# MCU098_05_XDS110_Target_Interface.net
KiCad netlist of a schematic drawn in Altium Designer
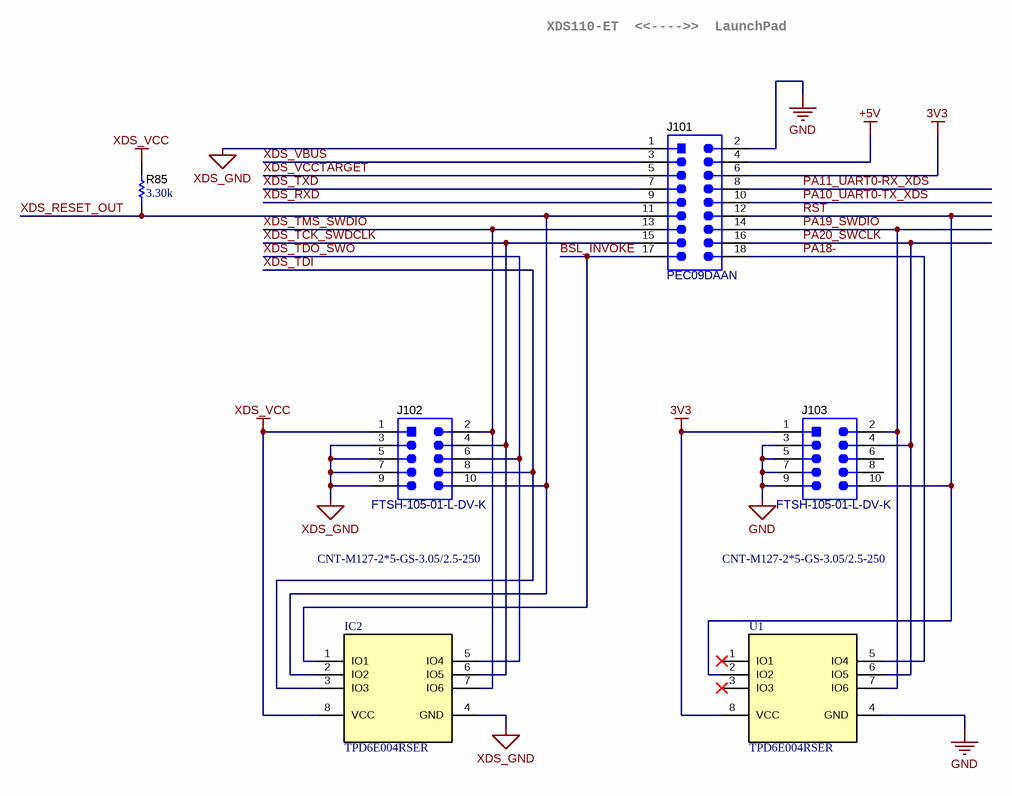
[diagram p0: MCU098_05_XDS110_Target_Interface.SchDoc]

(export (version "E")
  (design (tool "Eeschema 10.0.6"))
  (components
    (comp (ref "IC2")
      (value "TPD6E004RSER")
      (footprint "RSE0008A")
      (fields (field (name "MANUFACTURER") "Texas Instruments") (field (name "PARTNUMBER") "TPD6E004RSER"))
      (libsource (lib "Altium Vault - TI") (part "TI-TPD6E004-UQFN_RSE-8"))
    )
    (comp (ref "J101")
      (value "PEC09DAAN")
      (footprint "Sullins_PxC09DAAN")
      (description "Header, 2.54mm, 9x2, Tin, TH")
      (fields
        (field (name "MANUFACTURER") "Sullins Connector Solutions")
        (field (name "PUBLISHER") "Texas Instruments")
      )
      (libsource (lib "Altium Vault - TI") (part "Header_9x2"))
    )
    (comp (ref "J102")
      (value "FTSH-105-01-L-DV-K")
      (footprint "Samtec_FTSH-105-01-x-DV-K")
      (description "Header(Shrouded), 1.27mm, 5x2, Gold, SMT")
      (fields (field (name "MANUFACTURER") "Samtec") (field (name "PUBLISHER") "Texas Instruments"))
      (libsource (lib "Altium Vault - TI") (part "Header_5x2"))
    )
    (comp (ref "J103")
      (value "FTSH-105-01-L-DV-K")
      (footprint "Samtec_FTSH-105-01-x-DV-K")
      (description "Header(Shrouded), 1.27mm, 5x2, Gold, SMT")
      (fields (field (name "MANUFACTURER") "Samtec") (field (name "PUBLISHER") "Texas Instruments"))
      (libsource (lib "Altium Vault - TI") (part "Header_5x2"))
    )
    (comp (ref "R85")
      (value "ERJ-2RKF3301X")
      (footprint "0402")
      (description "RES, 3.30 k, 1%, 0.1 W, AEC-Q200 Grade 0, 0402")
      (fields
        (field (name "MANUFACTURER") "Panasonic")
        (field (name "VALUEDISPLAYED") "3.30k")
        (field (name "PUBLISHER") "Texas Instruments")
      )
      (libsource (lib "Altium Vault - TI") (part "Resistor"))
    )
    (comp (ref "U1")
      (value "TPD6E004RSER")
      (footprint "RSE0008A")
      (fields (field (name "MANUFACTURER") "Texas Instruments") (field (name "PARTNUMBER") "TPD6E004RSER"))
      (libsource (lib "Altium Vault - TI") (part "TI-TPD6E004-UQFN_RSE-8"))
    )
  )
  (nets
    (net (code "1") (name "+5V") (class "Default")
      (node (ref "J101") (pin "4") (pinfunction "4_4") (pintype "passive"))
    )
    (net (code "2") (name "/BSL_INVOKE") (class "Default")
      (node (ref "IC2") (pin "1") (pinfunction "IO1_1") (pintype "passive"))
      (node (ref "J101") (pin "17") (pinfunction "17_17") (pintype "passive"))
    )
    (net (code "3") (name "/PA10_UART0-TX_XDS") (class "Default")
      (node (ref "J101") (pin "10") (pinfunction "10_10") (pintype "passive"))
    )
    (net (code "4") (name "/PA11_UART0-RX_XDS") (class "Default")
      (node (ref "J101") (pin "8") (pinfunction "8_8") (pintype "passive"))
    )
    (net (code "5") (name "/PA18-") (class "Default")
      (node (ref "J101") (pin "18") (pinfunction "18_18") (pintype "passive"))
      (node (ref "U1") (pin "5") (pinfunction "IO4_5") (pintype "passive"))
    )
    (net (code "6") (name "/PA19_SWDIO") (class "Default")
      (node (ref "J101") (pin "14") (pinfunction "14_14") (pintype "passive"))
      (node (ref "J103") (pin "2") (pinfunction "2_2") (pintype "passive"))
      (node (ref "U1") (pin "7") (pinfunction "IO6_7") (pintype "passive"))
    )
    (net (code "7") (name "/PA20_SWCLK") (class "Default")
      (node (ref "J101") (pin "16") (pinfunction "16_16") (pintype "passive"))
      (node (ref "J103") (pin "4") (pinfunction "4_4") (pintype "passive"))
      (node (ref "U1") (pin "6") (pinfunction "IO5_6") (pintype "passive"))
    )
    (net (code "8") (name "/XDS_RESET_OUT") (class "Default")
      (node (ref "IC2") (pin "2") (pinfunction "IO2_2") (pintype "passive"))
      (node (ref "J101") (pin "11") (pinfunction "11_11") (pintype "passive"))
      (node (ref "J102") (pin "10") (pinfunction "10_10") (pintype "passive"))
      (node (ref "R85") (pin "1") (pinfunction "1_1") (pintype "passive"))
    )
    (net (code "9") (name "/XDS_RXD") (class "Default")
      (node (ref "J101") (pin "9") (pinfunction "9_9") (pintype "passive"))
    )
    (net (code "10") (name "/XDS_TCK_SWDCLK") (class "Default")
      (node (ref "IC2") (pin "6") (pinfunction "IO5_6") (pintype "passive"))
      (node (ref "J101") (pin "15") (pinfunction "15_15") (pintype "passive"))
      (node (ref "J102") (pin "4") (pinfunction "4_4") (pintype "passive"))
    )
    (net (code "11") (name "/XDS_TDI") (class "Default")
      (node (ref "IC2") (pin "3") (pinfunction "IO3_3") (pintype "passive"))
      (node (ref "J102") (pin "8") (pinfunction "8_8") (pintype "passive"))
    )
    (net (code "12") (name "/XDS_TDO_SWO") (class "Default")
      (node (ref "IC2") (pin "5") (pinfunction "IO4_5") (pintype "passive"))
      (node (ref "J102") (pin "6") (pinfunction "6_6") (pintype "passive"))
    )
    (net (code "13") (name "/XDS_TMS_SWDIO") (class "Default")
      (node (ref "IC2") (pin "7") (pinfunction "IO6_7") (pintype "passive"))
      (node (ref "J101") (pin "13") (pinfunction "13_13") (pintype "passive"))
      (node (ref "J102") (pin "2") (pinfunction "2_2") (pintype "passive"))
    )
    (net (code "14") (name "/XDS_TXD") (class "Default")
      (node (ref "J101") (pin "7") (pinfunction "7_7") (pintype "passive"))
    )
    (net (code "15") (name "/XDS_VBUS") (class "Default")
      (node (ref "J101") (pin "3") (pinfunction "3_3") (pintype "passive"))
    )
    (net (code "16") (name "/XDS_VCCTARGET") (class "Default")
      (node (ref "J101") (pin "5") (pinfunction "5_5") (pintype "passive"))
    )
    (net (code "17") (name "/~{RST}") (class "Default")
      (node (ref "J101") (pin "12") (pinfunction "12_12") (pintype "passive"))
      (node (ref "J103") (pin "10") (pinfunction "10_10") (pintype "passive"))
      (node (ref "U1") (pin "2") (pinfunction "IO2_2") (pintype "passive"))
    )
    (net (code "18") (name "3V3") (class "Default")
      (node (ref "J101") (pin "6") (pinfunction "6_6") (pintype "passive"))
      (node (ref "J103") (pin "1") (pinfunction "1_1") (pintype "passive"))
      (node (ref "U1") (pin "8") (pinfunction "VCC_8") (pintype "power_in"))
    )
    (net (code "19") (name "GND") (class "Default")
      (node (ref "J101") (pin "2") (pinfunction "2_2") (pintype "passive"))
      (node (ref "J103") (pin "3") (pinfunction "3_3") (pintype "passive"))
      (node (ref "J103") (pin "5") (pinfunction "5_5") (pintype "passive"))
      (node (ref "J103") (pin "7") (pinfunction "7_7") (pintype "passive"))
      (node (ref "J103") (pin "9") (pinfunction "9_9") (pintype "passive"))
      (node (ref "U1") (pin "4") (pinfunction "GND_4") (pintype "power_in"))
    )
    (net (code "20") (name "XDS_GND") (class "Default")
      (node (ref "IC2") (pin "4") (pinfunction "GND_4") (pintype "power_in"))
      (node (ref "J101") (pin "1") (pinfunction "1_1") (pintype "passive"))
      (node (ref "J102") (pin "3") (pinfunction "3_3") (pintype "passive"))
      (node (ref "J102") (pin "5") (pinfunction "5_5") (pintype "passive"))
      (node (ref "J102") (pin "7") (pinfunction "7_7") (pintype "passive"))
      (node (ref "J102") (pin "9") (pinfunction "9_9") (pintype "passive"))
    )
    (net (code "21") (name "XDS_VCC") (class "Default")
      (node (ref "IC2") (pin "8") (pinfunction "VCC_8") (pintype "power_in"))
      (node (ref "J102") (pin "1") (pinfunction "1_1") (pintype "passive"))
      (node (ref "R85") (pin "2") (pinfunction "2_2") (pintype "passive"))
    )
    (net (code "22") (name "unconnected-(J103-Pad6)") (class "Default")
      (node (ref "J103") (pin "6") (pinfunction "6_6") (pintype "passive"))
    )
    (net (code "23") (name "unconnected-(J103-Pad8)") (class "Default")
      (node (ref "J103") (pin "8") (pinfunction "8_8") (pintype "passive"))
    )
    (net (code "24") (name "unconnected-(U1-IO1-Pad1)") (class "Default")
      (node (ref "U1") (pin "1") (pinfunction "IO1_1") (pintype "passive+no_connect"))
    )
    (net (code "25") (name "unconnected-(U1-IO3-Pad3)") (class "Default")
      (node (ref "U1") (pin "3") (pinfunction "IO3_3") (pintype "passive+no_connect"))
    )
  )
)
